# YOTSUBA_GNSSantenna_ver_1_0.net
KiCad netlist of a schematic drawn in EAGLE
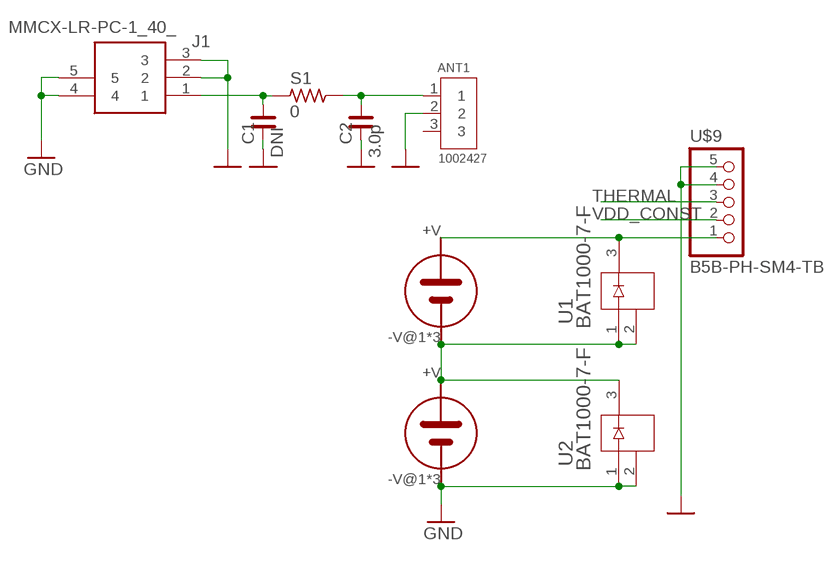
[diagram p0: schematic, sheet 1]

(export (version "E")
  (design (tool "Eeschema 10.0.6"))
  (components
    (comp (ref "ANT1")
      (value "1002427")
      (footprint "eagle-import:ANTENNA_1002427")
      (fields (field (name "DIGI-KEY_PART_NUMBER") "478-1002427TR-ND") (field (name "MF") "Ethertronics/AVX"))
      (libsource (lib "eagle-import") (part "1002427"))
    )
    (comp (ref "C1")
      (value "DNI")
      (footprint "eagle-import:C0603")
      (libsource (lib "eagle-import") (part "C_0603"))
    )
    (comp (ref "C2")
      (value "3.0p")
      (footprint "eagle-import:C0603")
      (libsource (lib "eagle-import") (part "C_0603"))
    )
    (comp (ref "J1")
      (value "MMCX-LR-PC-1_40_")
      (footprint "eagle-import:MMCXLRPC140")
      (fields
        (field (name "MANUFACTURER_PART_NUMBER") "MMCX-LR-PC-1(40)")
        (field (name "MOUSER_PART_NUMBER") "798-MMCX-LR-PC-1(40)")
      )
      (libsource (lib "eagle-import") (part "MMCX-LR-PC-1_40_"))
    )
    (comp (ref "S1")
      (value "0")
      (footprint "eagle-import:R0603")
      (libsource (lib "eagle-import") (part "R_0603"))
    )
    (comp (ref "U$2")
      (value "3G30A")
      (footprint "eagle-import:SOLAR_3G30A")
      (libsource (lib "eagle-import") (part "3G30A"))
    )
    (comp (ref "U$3")
      (value "3G30A")
      (footprint "eagle-import:SOLAR_3G30A")
      (libsource (lib "eagle-import") (part "3G30A"))
    )
    (comp (ref "U$9")
      (value "B5B-PH-SM4-TB")
      (footprint "eagle-import:B5B-PH-SM4-TB")
      (libsource (lib "eagle-import") (part "B5B-PH-SM4-TB"))
    )
    (comp (ref "U1")
      (value "BAT1000-7-F")
      (footprint "eagle-import:SOT23_BAT_DIO")
      (fields (field (name "COPYRIGHT") "Copyright (C) 2022 Ultra Librarian. All rights reserved."))
      (libsource (lib "eagle-import") (part "BAT1000-7-F"))
    )
    (comp (ref "U2")
      (value "BAT1000-7-F")
      (footprint "eagle-import:SOT23_BAT_DIO")
      (fields (field (name "COPYRIGHT") "Copyright (C) 2022 Ultra Librarian. All rights reserved."))
      (libsource (lib "eagle-import") (part "BAT1000-7-F"))
    )
  )
  (nets
    (net (code "1") (name "/THERMAL") (class "Default")
      (node (ref "U$9") (pin "3") (pinfunction "3_3") (pintype "passive"))
    )
    (net (code "2") (name "/VDD_CONST") (class "Default")
      (node (ref "U$9") (pin "2") (pinfunction "2_2") (pintype "passive"))
    )
    (net (code "3") (name "GND") (class "Default")
      (node (ref "ANT1") (pin "2") (pinfunction "2_2") (pintype "passive"))
      (node (ref "C1") (pin "1") (pinfunction "1_1") (pintype "passive"))
      (node (ref "C2") (pin "1") (pinfunction "1_1") (pintype "passive"))
      (node (ref "J1") (pin "2") (pinfunction "2_2") (pintype "bidirectional"))
      (node (ref "J1") (pin "3") (pinfunction "3_3") (pintype "bidirectional"))
      (node (ref "J1") (pin "4") (pinfunction "4_4") (pintype "bidirectional"))
      (node (ref "J1") (pin "5") (pinfunction "5_5") (pintype "bidirectional"))
      (node (ref "U$3") (pin "-V@1") (pinfunction "-V_-V@1") (pintype "bidirectional"))
      (node (ref "U$3") (pin "-V@2") (pinfunction "-V_-V@2") (pintype "bidirectional"))
      (node (ref "U$3") (pin "-V@3") (pinfunction "-V_-V@3") (pintype "bidirectional"))
      (node (ref "U$9") (pin "4") (pinfunction "4_4") (pintype "passive"))
      (node (ref "U$9") (pin "5") (pinfunction "5_5") (pintype "passive"))
      (node (ref "U2") (pin "1") (pinfunction "1_1") (pintype "passive"))
      (node (ref "U2") (pin "2") (pinfunction "2_2") (pintype "passive"))
    )
    (net (code "4") (name "Net-(ANT1-Pad1)") (class "Default")
      (node (ref "ANT1") (pin "1") (pinfunction "1_1") (pintype "passive"))
      (node (ref "C2") (pin "2") (pinfunction "2_2") (pintype "passive"))
      (node (ref "S1") (pin "2") (pinfunction "2_2") (pintype "passive"))
    )
    (net (code "5") (name "Net-(C1-Pad2)") (class "Default")
      (node (ref "C1") (pin "2") (pinfunction "2_2") (pintype "passive"))
      (node (ref "J1") (pin "1") (pinfunction "1_1") (pintype "bidirectional"))
      (node (ref "S1") (pin "1") (pinfunction "1_1") (pintype "passive"))
    )
    (net (code "6") (name "Net-(U$2--V-Pad-V@1)") (class "Default")
      (node (ref "U$2") (pin "-V@1") (pinfunction "-V_-V@1") (pintype "bidirectional"))
      (node (ref "U$2") (pin "-V@2") (pinfunction "-V_-V@2") (pintype "bidirectional"))
      (node (ref "U$2") (pin "-V@3") (pinfunction "-V_-V@3") (pintype "bidirectional"))
      (node (ref "U$3") (pin "+V") (pinfunction "+V_+V") (pintype "bidirectional"))
      (node (ref "U1") (pin "1") (pinfunction "1_1") (pintype "passive"))
      (node (ref "U1") (pin "2") (pinfunction "2_2") (pintype "passive"))
      (node (ref "U2") (pin "3") (pinfunction "3_3") (pintype "passive"))
    )
    (net (code "7") (name "Net-(U$2-Pad+V)") (class "Default")
      (node (ref "U$2") (pin "+V") (pinfunction "+V_+V") (pintype "bidirectional"))
      (node (ref "U$9") (pin "1") (pinfunction "1_1") (pintype "passive"))
      (node (ref "U1") (pin "3") (pinfunction "3_3") (pintype "passive"))
    )
    (net (code "8") (name "unconnected-(ANT1-Pad3)") (class "Default")
      (node (ref "ANT1") (pin "3") (pinfunction "3_3") (pintype "passive"))
    )
  )
)
